# edge.net
KiCad netlist of a schematic drawn in Altium Designer
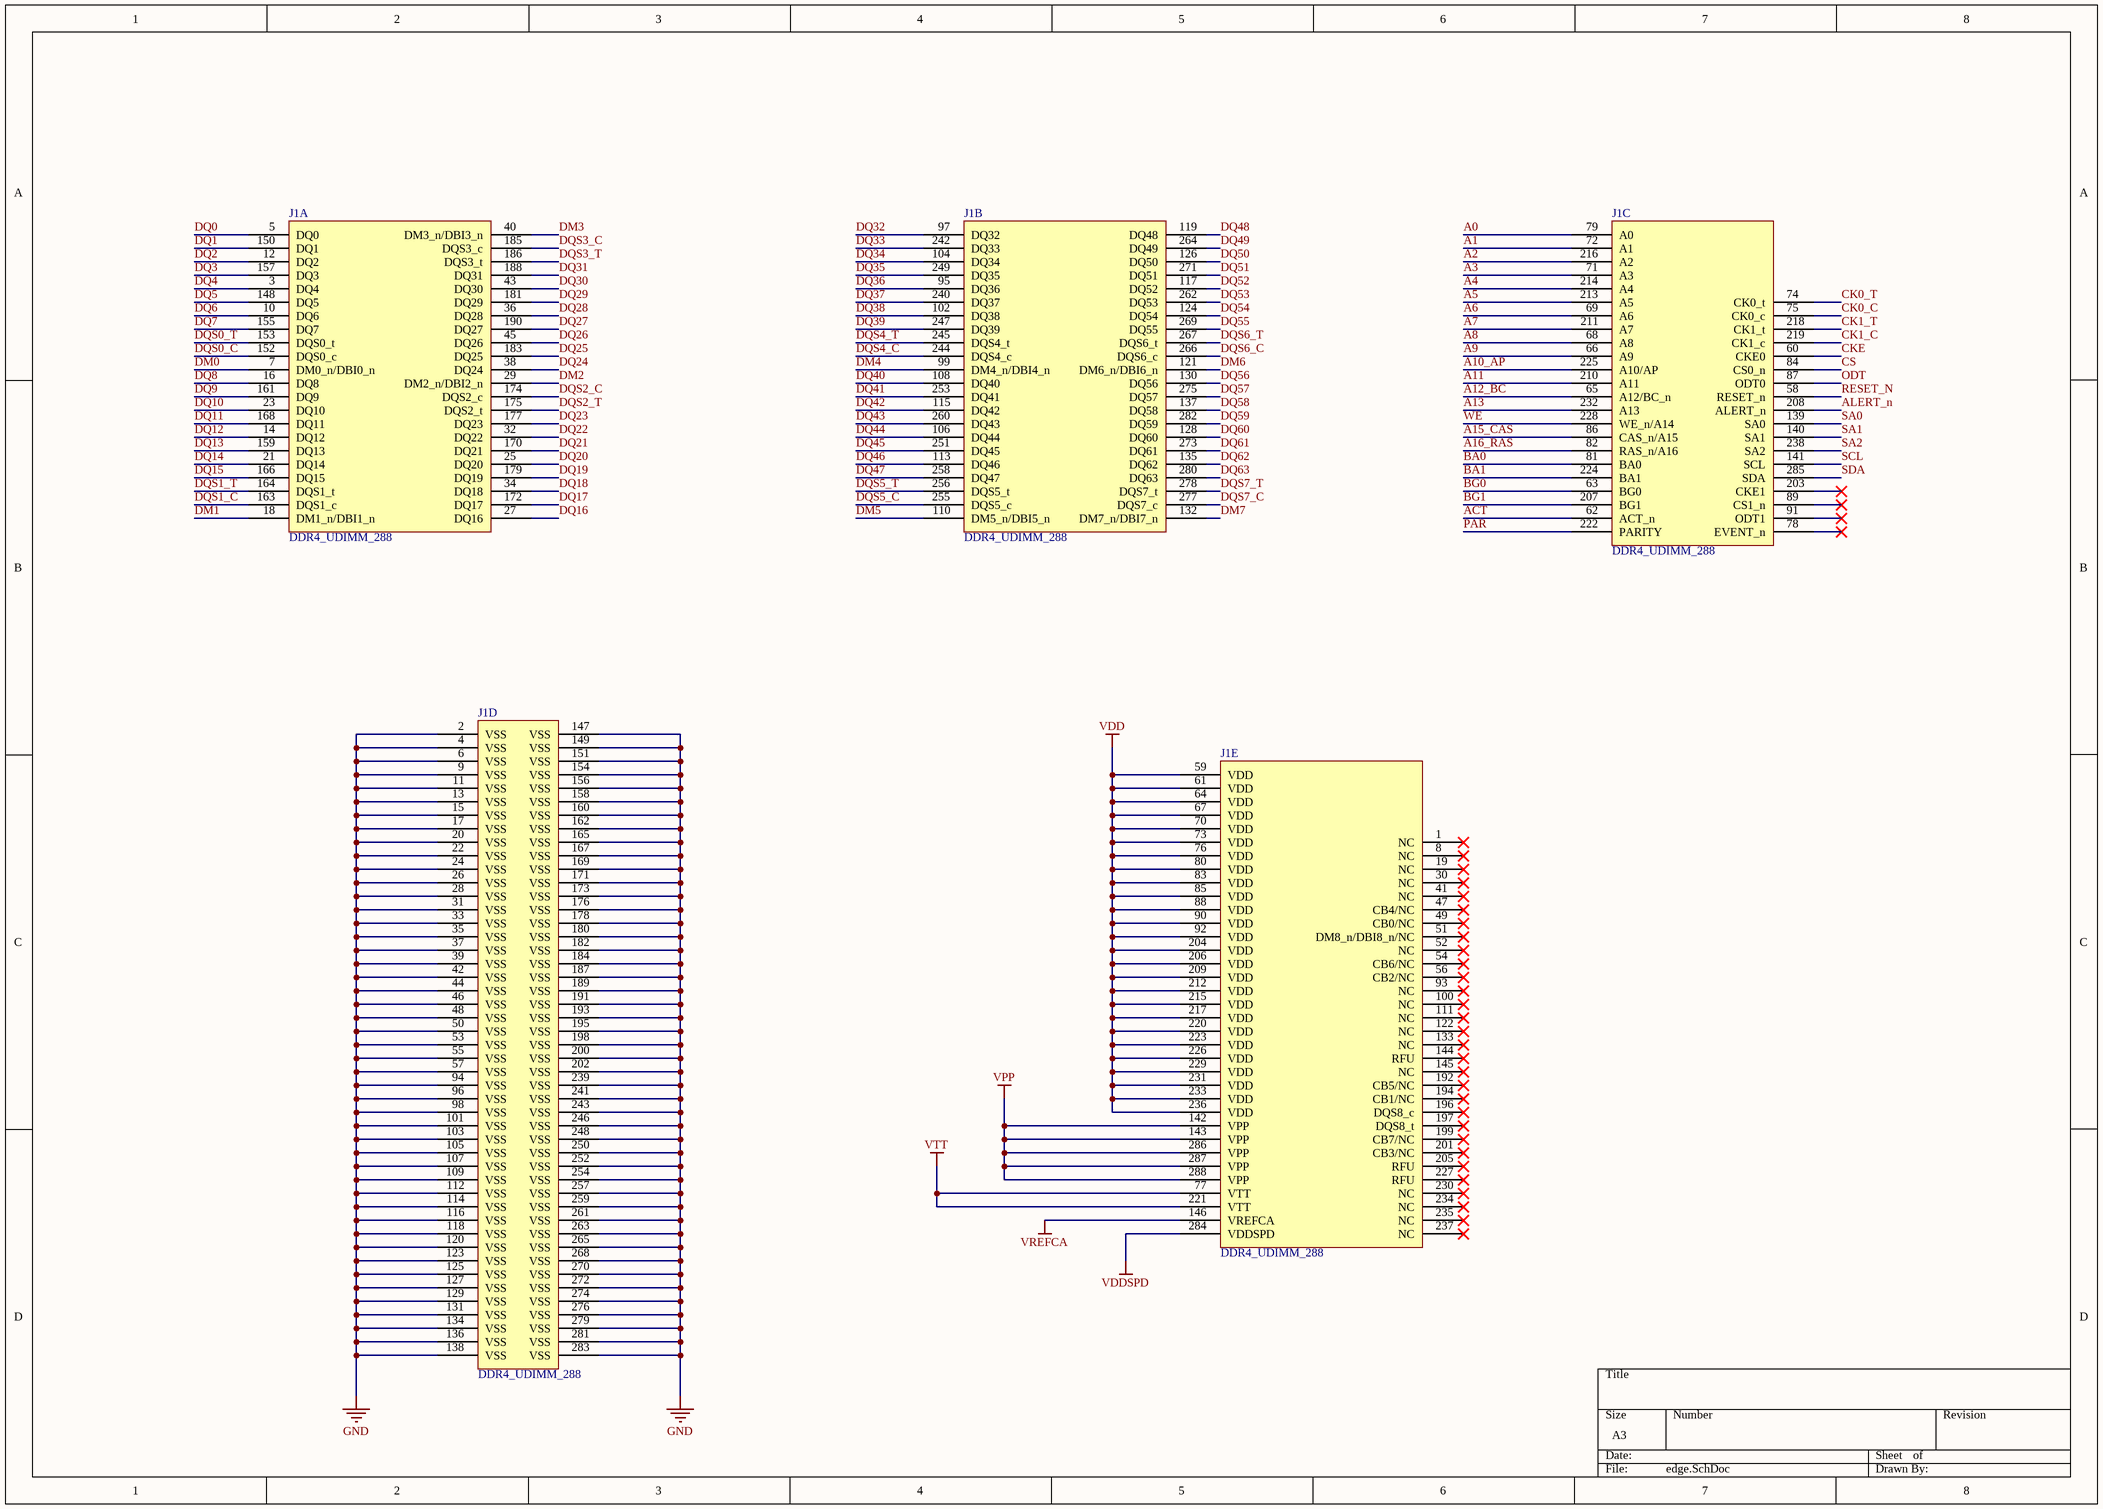
[diagram p0: edge.SchDoc]

(export (version "E")
  (design (tool "Eeschema 10.0.6"))
  (components
    (comp (ref "J1")
      (value "DDR4_UDIMM_288")
      (footprint "DDR4_UDIMM_288_MO309")
      (description "DDR4 288-pin UDIMM edge fingers, 0.85 mm pitch (JEDEC MO-309)")
      (libsource (lib "DDR4_UDIMM") (part "Component_1"))
    )
  )
  (nets
    (net (code "1") (name "/A0") (class "Default")
      (node (ref "J1") (pin "79") (pinfunction "A0_79") (pintype "passive"))
    )
    (net (code "2") (name "/A1") (class "Default")
      (node (ref "J1") (pin "72") (pinfunction "A1_72") (pintype "passive"))
    )
    (net (code "3") (name "/A2") (class "Default")
      (node (ref "J1") (pin "216") (pinfunction "A2_216") (pintype "passive"))
    )
    (net (code "4") (name "/A3") (class "Default")
      (node (ref "J1") (pin "71") (pinfunction "A3_71") (pintype "passive"))
    )
    (net (code "5") (name "/A4") (class "Default")
      (node (ref "J1") (pin "214") (pinfunction "A4_214") (pintype "passive"))
    )
    (net (code "6") (name "/A5") (class "Default")
      (node (ref "J1") (pin "213") (pinfunction "A5_213") (pintype "passive"))
    )
    (net (code "7") (name "/A6") (class "Default")
      (node (ref "J1") (pin "69") (pinfunction "A6_69") (pintype "passive"))
    )
    (net (code "8") (name "/A7") (class "Default")
      (node (ref "J1") (pin "211") (pinfunction "A7_211") (pintype "passive"))
    )
    (net (code "9") (name "/A8") (class "Default")
      (node (ref "J1") (pin "68") (pinfunction "A8_68") (pintype "passive"))
    )
    (net (code "10") (name "/A9") (class "Default")
      (node (ref "J1") (pin "66") (pinfunction "A9_66") (pintype "passive"))
    )
    (net (code "11") (name "/A10_AP") (class "Default")
      (node (ref "J1") (pin "225") (pinfunction "A10/AP_225") (pintype "passive"))
    )
    (net (code "12") (name "/A11") (class "Default")
      (node (ref "J1") (pin "210") (pinfunction "A11_210") (pintype "passive"))
    )
    (net (code "13") (name "/A12_BC") (class "Default")
      (node (ref "J1") (pin "65") (pinfunction "A12/BC_n_65") (pintype "passive"))
    )
    (net (code "14") (name "/A13") (class "Default")
      (node (ref "J1") (pin "232") (pinfunction "A13_232") (pintype "passive"))
    )
    (net (code "15") (name "/A15_CAS") (class "Default")
      (node (ref "J1") (pin "86") (pinfunction "CAS_n/A15_86") (pintype "passive"))
    )
    (net (code "16") (name "/A16_RAS") (class "Default")
      (node (ref "J1") (pin "82") (pinfunction "RAS_n/A16_82") (pintype "passive"))
    )
    (net (code "17") (name "/ACT") (class "Default")
      (node (ref "J1") (pin "62") (pinfunction "ACT_n_62") (pintype "passive"))
    )
    (net (code "18") (name "/ALERT_n") (class "Default")
      (node (ref "J1") (pin "208") (pinfunction "ALERT_n_208") (pintype "passive"))
    )
    (net (code "19") (name "/BA0") (class "Default")
      (node (ref "J1") (pin "81") (pinfunction "BA0_81") (pintype "passive"))
    )
    (net (code "20") (name "/BA1") (class "Default")
      (node (ref "J1") (pin "224") (pinfunction "BA1_224") (pintype "passive"))
    )
    (net (code "21") (name "/BG0") (class "Default")
      (node (ref "J1") (pin "63") (pinfunction "BG0_63") (pintype "passive"))
    )
    (net (code "22") (name "/BG1") (class "Default")
      (node (ref "J1") (pin "207") (pinfunction "BG1_207") (pintype "passive"))
    )
    (net (code "23") (name "/CK0_C") (class "Default")
      (node (ref "J1") (pin "75") (pinfunction "CK0_c_75") (pintype "passive"))
    )
    (net (code "24") (name "/CK0_T") (class "Default")
      (node (ref "J1") (pin "74") (pinfunction "CK0_t_74") (pintype "passive"))
    )
    (net (code "25") (name "/CK1_C") (class "Default")
      (node (ref "J1") (pin "219") (pinfunction "CK1_c_219") (pintype "passive"))
    )
    (net (code "26") (name "/CK1_T") (class "Default")
      (node (ref "J1") (pin "218") (pinfunction "CK1_t_218") (pintype "passive"))
    )
    (net (code "27") (name "/CKE") (class "Default")
      (node (ref "J1") (pin "60") (pinfunction "CKE0_60") (pintype "passive"))
    )
    (net (code "28") (name "/CS") (class "Default")
      (node (ref "J1") (pin "84") (pinfunction "CS0_n_84") (pintype "passive"))
    )
    (net (code "29") (name "/DM0") (class "Default")
      (node (ref "J1") (pin "7") (pinfunction "DM0_n/DBI0_n_7") (pintype "passive"))
    )
    (net (code "30") (name "/DM1") (class "Default")
      (node (ref "J1") (pin "18") (pinfunction "DM1_n/DBI1_n_18") (pintype "passive"))
    )
    (net (code "31") (name "/DM2") (class "Default")
      (node (ref "J1") (pin "29") (pinfunction "DM2_n/DBI2_n_29") (pintype "passive"))
    )
    (net (code "32") (name "/DM3") (class "Default")
      (node (ref "J1") (pin "40") (pinfunction "DM3_n/DBI3_n_40") (pintype "passive"))
    )
    (net (code "33") (name "/DM4") (class "Default")
      (node (ref "J1") (pin "99") (pinfunction "DM4_n/DBI4_n_99") (pintype "passive"))
    )
    (net (code "34") (name "/DM5") (class "Default")
      (node (ref "J1") (pin "110") (pinfunction "DM5_n/DBI5_n_110") (pintype "passive"))
    )
    (net (code "35") (name "/DM6") (class "Default")
      (node (ref "J1") (pin "121") (pinfunction "DM6_n/DBI6_n_121") (pintype "passive"))
    )
    (net (code "36") (name "/DM7") (class "Default")
      (node (ref "J1") (pin "132") (pinfunction "DM7_n/DBI7_n_132") (pintype "passive"))
    )
    (net (code "37") (name "/DQ0") (class "Default")
      (node (ref "J1") (pin "5") (pinfunction "DQ0_5") (pintype "passive"))
    )
    (net (code "38") (name "/DQ1") (class "Default")
      (node (ref "J1") (pin "150") (pinfunction "DQ1_150") (pintype "passive"))
    )
    (net (code "39") (name "/DQ2") (class "Default")
      (node (ref "J1") (pin "12") (pinfunction "DQ2_12") (pintype "passive"))
    )
    (net (code "40") (name "/DQ3") (class "Default")
      (node (ref "J1") (pin "157") (pinfunction "DQ3_157") (pintype "passive"))
    )
    (net (code "41") (name "/DQ4") (class "Default")
      (node (ref "J1") (pin "3") (pinfunction "DQ4_3") (pintype "passive"))
    )
    (net (code "42") (name "/DQ5") (class "Default")
      (node (ref "J1") (pin "148") (pinfunction "DQ5_148") (pintype "passive"))
    )
    (net (code "43") (name "/DQ6") (class "Default")
      (node (ref "J1") (pin "10") (pinfunction "DQ6_10") (pintype "passive"))
    )
    (net (code "44") (name "/DQ7") (class "Default")
      (node (ref "J1") (pin "155") (pinfunction "DQ7_155") (pintype "passive"))
    )
    (net (code "45") (name "/DQ8") (class "Default")
      (node (ref "J1") (pin "16") (pinfunction "DQ8_16") (pintype "passive"))
    )
    (net (code "46") (name "/DQ9") (class "Default")
      (node (ref "J1") (pin "161") (pinfunction "DQ9_161") (pintype "passive"))
    )
    (net (code "47") (name "/DQ10") (class "Default")
      (node (ref "J1") (pin "23") (pinfunction "DQ10_23") (pintype "passive"))
    )
    (net (code "48") (name "/DQ11") (class "Default")
      (node (ref "J1") (pin "168") (pinfunction "DQ11_168") (pintype "passive"))
    )
    (net (code "49") (name "/DQ12") (class "Default")
      (node (ref "J1") (pin "14") (pinfunction "DQ12_14") (pintype "passive"))
    )
    (net (code "50") (name "/DQ13") (class "Default")
      (node (ref "J1") (pin "159") (pinfunction "DQ13_159") (pintype "passive"))
    )
    (net (code "51") (name "/DQ14") (class "Default")
      (node (ref "J1") (pin "21") (pinfunction "DQ14_21") (pintype "passive"))
    )
    (net (code "52") (name "/DQ15") (class "Default")
      (node (ref "J1") (pin "166") (pinfunction "DQ15_166") (pintype "passive"))
    )
    (net (code "53") (name "/DQ16") (class "Default")
      (node (ref "J1") (pin "27") (pinfunction "DQ16_27") (pintype "passive"))
    )
    (net (code "54") (name "/DQ17") (class "Default")
      (node (ref "J1") (pin "172") (pinfunction "DQ17_172") (pintype "passive"))
    )
    (net (code "55") (name "/DQ18") (class "Default")
      (node (ref "J1") (pin "34") (pinfunction "DQ18_34") (pintype "passive"))
    )
    (net (code "56") (name "/DQ19") (class "Default")
      (node (ref "J1") (pin "179") (pinfunction "DQ19_179") (pintype "passive"))
    )
    (net (code "57") (name "/DQ20") (class "Default")
      (node (ref "J1") (pin "25") (pinfunction "DQ20_25") (pintype "passive"))
    )
    (net (code "58") (name "/DQ21") (class "Default")
      (node (ref "J1") (pin "170") (pinfunction "DQ21_170") (pintype "passive"))
    )
    (net (code "59") (name "/DQ22") (class "Default")
      (node (ref "J1") (pin "32") (pinfunction "DQ22_32") (pintype "passive"))
    )
    (net (code "60") (name "/DQ23") (class "Default")
      (node (ref "J1") (pin "177") (pinfunction "DQ23_177") (pintype "passive"))
    )
    (net (code "61") (name "/DQ24") (class "Default")
      (node (ref "J1") (pin "38") (pinfunction "DQ24_38") (pintype "passive"))
    )
    (net (code "62") (name "/DQ25") (class "Default")
      (node (ref "J1") (pin "183") (pinfunction "DQ25_183") (pintype "passive"))
    )
    (net (code "63") (name "/DQ26") (class "Default")
      (node (ref "J1") (pin "45") (pinfunction "DQ26_45") (pintype "passive"))
    )
    (net (code "64") (name "/DQ27") (class "Default")
      (node (ref "J1") (pin "190") (pinfunction "DQ27_190") (pintype "passive"))
    )
    (net (code "65") (name "/DQ28") (class "Default")
      (node (ref "J1") (pin "36") (pinfunction "DQ28_36") (pintype "passive"))
    )
    (net (code "66") (name "/DQ29") (class "Default")
      (node (ref "J1") (pin "181") (pinfunction "DQ29_181") (pintype "passive"))
    )
    (net (code "67") (name "/DQ30") (class "Default")
      (node (ref "J1") (pin "43") (pinfunction "DQ30_43") (pintype "passive"))
    )
    (net (code "68") (name "/DQ31") (class "Default")
      (node (ref "J1") (pin "188") (pinfunction "DQ31_188") (pintype "passive"))
    )
    (net (code "69") (name "/DQ32") (class "Default")
      (node (ref "J1") (pin "97") (pinfunction "DQ32_97") (pintype "passive"))
    )
    (net (code "70") (name "/DQ33") (class "Default")
      (node (ref "J1") (pin "242") (pinfunction "DQ33_242") (pintype "passive"))
    )
    (net (code "71") (name "/DQ34") (class "Default")
      (node (ref "J1") (pin "104") (pinfunction "DQ34_104") (pintype "passive"))
    )
    (net (code "72") (name "/DQ35") (class "Default")
      (node (ref "J1") (pin "249") (pinfunction "DQ35_249") (pintype "passive"))
    )
    (net (code "73") (name "/DQ36") (class "Default")
      (node (ref "J1") (pin "95") (pinfunction "DQ36_95") (pintype "passive"))
    )
    (net (code "74") (name "/DQ37") (class "Default")
      (node (ref "J1") (pin "240") (pinfunction "DQ37_240") (pintype "passive"))
    )
    (net (code "75") (name "/DQ38") (class "Default")
      (node (ref "J1") (pin "102") (pinfunction "DQ38_102") (pintype "passive"))
    )
    (net (code "76") (name "/DQ39") (class "Default")
      (node (ref "J1") (pin "247") (pinfunction "DQ39_247") (pintype "passive"))
    )
    (net (code "77") (name "/DQ40") (class "Default")
      (node (ref "J1") (pin "108") (pinfunction "DQ40_108") (pintype "passive"))
    )
    (net (code "78") (name "/DQ41") (class "Default")
      (node (ref "J1") (pin "253") (pinfunction "DQ41_253") (pintype "passive"))
    )
    (net (code "79") (name "/DQ42") (class "Default")
      (node (ref "J1") (pin "115") (pinfunction "DQ42_115") (pintype "passive"))
    )
    (net (code "80") (name "/DQ43") (class "Default")
      (node (ref "J1") (pin "260") (pinfunction "DQ43_260") (pintype "passive"))
    )
    (net (code "81") (name "/DQ44") (class "Default")
      (node (ref "J1") (pin "106") (pinfunction "DQ44_106") (pintype "passive"))
    )
    (net (code "82") (name "/DQ45") (class "Default")
      (node (ref "J1") (pin "251") (pinfunction "DQ45_251") (pintype "passive"))
    )
    (net (code "83") (name "/DQ46") (class "Default")
      (node (ref "J1") (pin "113") (pinfunction "DQ46_113") (pintype "passive"))
    )
    (net (code "84") (name "/DQ47") (class "Default")
      (node (ref "J1") (pin "258") (pinfunction "DQ47_258") (pintype "passive"))
    )
    (net (code "85") (name "/DQ48") (class "Default")
      (node (ref "J1") (pin "119") (pinfunction "DQ48_119") (pintype "passive"))
    )
    (net (code "86") (name "/DQ49") (class "Default")
      (node (ref "J1") (pin "264") (pinfunction "DQ49_264") (pintype "passive"))
    )
    (net (code "87") (name "/DQ50") (class "Default")
      (node (ref "J1") (pin "126") (pinfunction "DQ50_126") (pintype "passive"))
    )
    (net (code "88") (name "/DQ51") (class "Default")
      (node (ref "J1") (pin "271") (pinfunction "DQ51_271") (pintype "passive"))
    )
    (net (code "89") (name "/DQ52") (class "Default")
      (node (ref "J1") (pin "117") (pinfunction "DQ52_117") (pintype "passive"))
    )
    (net (code "90") (name "/DQ53") (class "Default")
      (node (ref "J1") (pin "262") (pinfunction "DQ53_262") (pintype "passive"))
    )
    (net (code "91") (name "/DQ54") (class "Default")
      (node (ref "J1") (pin "124") (pinfunction "DQ54_124") (pintype "passive"))
    )
    (net (code "92") (name "/DQ55") (class "Default")
      (node (ref "J1") (pin "269") (pinfunction "DQ55_269") (pintype "passive"))
    )
    (net (code "93") (name "/DQ56") (class "Default")
      (node (ref "J1") (pin "130") (pinfunction "DQ56_130") (pintype "passive"))
    )
    (net (code "94") (name "/DQ57") (class "Default")
      (node (ref "J1") (pin "275") (pinfunction "DQ57_275") (pintype "passive"))
    )
    (net (code "95") (name "/DQ58") (class "Default")
      (node (ref "J1") (pin "137") (pinfunction "DQ58_137") (pintype "passive"))
    )
    (net (code "96") (name "/DQ59") (class "Default")
      (node (ref "J1") (pin "282") (pinfunction "DQ59_282") (pintype "passive"))
    )
    (net (code "97") (name "/DQ60") (class "Default")
      (node (ref "J1") (pin "128") (pinfunction "DQ60_128") (pintype "passive"))
    )
    (net (code "98") (name "/DQ61") (class "Default")
      (node (ref "J1") (pin "273") (pinfunction "DQ61_273") (pintype "passive"))
    )
    (net (code "99") (name "/DQ62") (class "Default")
      (node (ref "J1") (pin "135") (pinfunction "DQ62_135") (pintype "passive"))
    )
    (net (code "100") (name "/DQ63") (class "Default")
      (node (ref "J1") (pin "280") (pinfunction "DQ63_280") (pintype "passive"))
    )
    (net (code "101") (name "/DQS0_C") (class "Default")
      (node (ref "J1") (pin "152") (pinfunction "DQS0_c_152") (pintype "passive"))
    )
    (net (code "102") (name "/DQS0_T") (class "Default")
      (node (ref "J1") (pin "153") (pinfunction "DQS0_t_153") (pintype "passive"))
    )
    (net (code "103") (name "/DQS1_C") (class "Default")
      (node (ref "J1") (pin "163") (pinfunction "DQS1_c_163") (pintype "passive"))
    )
    (net (code "104") (name "/DQS1_T") (class "Default")
      (node (ref "J1") (pin "164") (pinfunction "DQS1_t_164") (pintype "passive"))
    )
    (net (code "105") (name "/DQS2_C") (class "Default")
      (node (ref "J1") (pin "174") (pinfunction "DQS2_c_174") (pintype "passive"))
    )
    (net (code "106") (name "/DQS2_T") (class "Default")
      (node (ref "J1") (pin "175") (pinfunction "DQS2_t_175") (pintype "passive"))
    )
    (net (code "107") (name "/DQS3_C") (class "Default")
      (node (ref "J1") (pin "185") (pinfunction "DQS3_c_185") (pintype "passive"))
    )
    (net (code "108") (name "/DQS3_T") (class "Default")
      (node (ref "J1") (pin "186") (pinfunction "DQS3_t_186") (pintype "passive"))
    )
    (net (code "109") (name "/DQS4_C") (class "Default")
      (node (ref "J1") (pin "244") (pinfunction "DQS4_c_244") (pintype "passive"))
    )
    (net (code "110") (name "/DQS4_T") (class "Default")
      (node (ref "J1") (pin "245") (pinfunction "DQS4_t_245") (pintype "passive"))
    )
    (net (code "111") (name "/DQS5_C") (class "Default")
      (node (ref "J1") (pin "255") (pinfunction "DQS5_c_255") (pintype "passive"))
    )
    (net (code "112") (name "/DQS5_T") (class "Default")
      (node (ref "J1") (pin "256") (pinfunction "DQS5_t_256") (pintype "passive"))
    )
    (net (code "113") (name "/DQS6_C") (class "Default")
      (node (ref "J1") (pin "266") (pinfunction "DQS6_c_266") (pintype "passive"))
    )
    (net (code "114") (name "/DQS6_T") (class "Default")
      (node (ref "J1") (pin "267") (pinfunction "DQS6_t_267") (pintype "passive"))
    )
    (net (code "115") (name "/DQS7_C") (class "Default")
      (node (ref "J1") (pin "277") (pinfunction "DQS7_c_277") (pintype "passive"))
    )
    (net (code "116") (name "/DQS7_T") (class "Default")
      (node (ref "J1") (pin "278") (pinfunction "DQS7_t_278") (pintype "passive"))
    )
    (net (code "117") (name "/ODT") (class "Default")
      (node (ref "J1") (pin "87") (pinfunction "ODT0_87") (pintype "passive"))
    )
    (net (code "118") (name "/PAR") (class "Default")
      (node (ref "J1") (pin "222") (pinfunction "PARITY_222") (pintype "passive"))
    )
    (net (code "119") (name "/RESET_N") (class "Default")
      (node (ref "J1") (pin "58") (pinfunction "RESET_n_58") (pintype "passive"))
    )
    (net (code "120") (name "/SA0") (class "Default")
      (node (ref "J1") (pin "139") (pinfunction "SA0_139") (pintype "passive"))
    )
    (net (code "121") (name "/SA1") (class "Default")
      (node (ref "J1") (pin "140") (pinfunction "SA1_140") (pintype "passive"))
    )
    (net (code "122") (name "/SA2") (class "Default")
      (node (ref "J1") (pin "238") (pinfunction "SA2_238") (pintype "passive"))
    )
    (net (code "123") (name "/SCL") (class "Default")
      (node (ref "J1") (pin "141") (pinfunction "SCL_141") (pintype "passive"))
    )
    (net (code "124") (name "/SDA") (class "Default")
      (node (ref "J1") (pin "285") (pinfunction "SDA_285") (pintype "passive"))
    )
    (net (code "125") (name "/WE") (class "Default")
      (node (ref "J1") (pin "228") (pinfunction "WE_n/A14_228") (pintype "passive"))
    )
    (net (code "126") (name "GND") (class "Default")
      (node (ref "J1") (pin "101") (pinfunction "VSS_101") (pintype "passive"))
      (node (ref "J1") (pin "103") (pinfunction "VSS_103") (pintype "passive"))
      (node (ref "J1") (pin "105") (pinfunction "VSS_105") (pintype "passive"))
      (node (ref "J1") (pin "107") (pinfunction "VSS_107") (pintype "passive"))
      (node (ref "J1") (pin "109") (pinfunction "VSS_109") (pintype "passive"))
      (node (ref "J1") (pin "11") (pinfunction "VSS_11") (pintype "passive"))
      (node (ref "J1") (pin "112") (pinfunction "VSS_112") (pintype "passive"))
      (node (ref "J1") (pin "114") (pinfunction "VSS_114") (pintype "passive"))
      (node (ref "J1") (pin "116") (pinfunction "VSS_116") (pintype "passive"))
      (node (ref "J1") (pin "118") (pinfunction "VSS_118") (pintype "passive"))
      (node (ref "J1") (pin "120") (pinfunction "VSS_120") (pintype "passive"))
      (node (ref "J1") (pin "123") (pinfunction "VSS_123") (pintype "passive"))
      (node (ref "J1") (pin "125") (pinfunction "VSS_125") (pintype "passive"))
      (node (ref "J1") (pin "127") (pinfunction "VSS_127") (pintype "passive"))
      (node (ref "J1") (pin "129") (pinfunction "VSS_129") (pintype "passive"))
      (node (ref "J1") (pin "13") (pinfunction "VSS_13") (pintype "passive"))
      (node (ref "J1") (pin "131") (pinfunction "VSS_131") (pintype "passive"))
      (node (ref "J1") (pin "134") (pinfunction "VSS_134") (pintype "passive"))
      (node (ref "J1") (pin "136") (pinfunction "VSS_136") (pintype "passive"))
      (node (ref "J1") (pin "138") (pinfunction "VSS_138") (pintype "passive"))
      (node (ref "J1") (pin "147") (pinfunction "VSS_147") (pintype "passive"))
      (node (ref "J1") (pin "149") (pinfunction "VSS_149") (pintype "passive"))
      (node (ref "J1") (pin "15") (pinfunction "VSS_15") (pintype "passive"))
      (node (ref "J1") (pin "151") (pinfunction "VSS_151") (pintype "passive"))
      (node (ref "J1") (pin "154") (pinfunction "VSS_154") (pintype "passive"))
      (node (ref "J1") (pin "156") (pinfunction "VSS_156") (pintype "passive"))
      (node (ref "J1") (pin "158") (pinfunction "VSS_158") (pintype "passive"))
      (node (ref "J1") (pin "160") (pinfunction "VSS_160") (pintype "passive"))
      (node (ref "J1") (pin "162") (pinfunction "VSS_162") (pintype "passive"))
      (node (ref "J1") (pin "165") (pinfunction "VSS_165") (pintype "passive"))
      (node (ref "J1") (pin "167") (pinfunction "VSS_167") (pintype "passive"))
      (node (ref "J1") (pin "169") (pinfunction "VSS_169") (pintype "passive"))
      (node (ref "J1") (pin "17") (pinfunction "VSS_17") (pintype "passive"))
      (node (ref "J1") (pin "171") (pinfunction "VSS_171") (pintype "passive"))
      (node (ref "J1") (pin "173") (pinfunction "VSS_173") (pintype "passive"))
      (node (ref "J1") (pin "176") (pinfunction "VSS_176") (pintype "passive"))
      (node (ref "J1") (pin "178") (pinfunction "VSS_178") (pintype "passive"))
      (node (ref "J1") (pin "180") (pinfunction "VSS_180") (pintype "passive"))
      (node (ref "J1") (pin "182") (pinfunction "VSS_182") (pintype "passive"))
      (node (ref "J1") (pin "184") (pinfunction "VSS_184") (pintype "passive"))
      (node (ref "J1") (pin "187") (pinfunction "VSS_187") (pintype "passive"))
      (node (ref "J1") (pin "189") (pinfunction "VSS_189") (pintype "passive"))
      (node (ref "J1") (pin "191") (pinfunction "VSS_191") (pintype "passive"))
      (node (ref "J1") (pin "193") (pinfunction "VSS_193") (pintype "passive"))
      (node (ref "J1") (pin "195") (pinfunction "VSS_195") (pintype "passive"))
      (node (ref "J1") (pin "198") (pinfunction "VSS_198") (pintype "passive"))
      (node (ref "J1") (pin "2") (pinfunction "VSS_2") (pintype "passive"))
      (node (ref "J1") (pin "20") (pinfunction "VSS_20") (pintype "passive"))
      (node (ref "J1") (pin "200") (pinfunction "VSS_200") (pintype "passive"))
      (node (ref "J1") (pin "202") (pinfunction "VSS_202") (pintype "passive"))
      (node (ref "J1") (pin "22") (pinfunction "VSS_22") (pintype "passive"))
      (node (ref "J1") (pin "239") (pinfunction "VSS_239") (pintype "passive"))
      (node (ref "J1") (pin "24") (pinfunction "VSS_24") (pintype "passive"))
      (node (ref "J1") (pin "241") (pinfunction "VSS_241") (pintype "passive"))
      (node (ref "J1") (pin "243") (pinfunction "VSS_243") (pintype "passive"))
      (node (ref "J1") (pin "246") (pinfunction "VSS_246") (pintype "passive"))
      (node (ref "J1") (pin "248") (pinfunction "VSS_248") (pintype "passive"))
      (node (ref "J1") (pin "250") (pinfunction "VSS_250") (pintype "passive"))
      (node (ref "J1") (pin "252") (pinfunction "VSS_252") (pintype "passive"))
      (node (ref "J1") (pin "254") (pinfunction "VSS_254") (pintype "passive"))
      (node (ref "J1") (pin "257") (pinfunction "VSS_257") (pintype "passive"))
      (node (ref "J1") (pin "259") (pinfunction "VSS_259") (pintype "passive"))
      (node (ref "J1") (pin "26") (pinfunction "VSS_26") (pintype "passive"))
      (node (ref "J1") (pin "261") (pinfunction "VSS_261") (pintype "passive"))
      (node (ref "J1") (pin "263") (pinfunction "VSS_263") (pintype "passive"))
      (node (ref "J1") (pin "265") (pinfunction "VSS_265") (pintype "passive"))
      (node (ref "J1") (pin "268") (pinfunction "VSS_268") (pintype "passive"))
      (node (ref "J1") (pin "270") (pinfunction "VSS_270") (pintype "passive"))
      (node (ref "J1") (pin "272") (pinfunction "VSS_272") (pintype "passive"))
      (node (ref "J1") (pin "274") (pinfunction "VSS_274") (pintype "passive"))
      (node (ref "J1") (pin "276") (pinfunction "VSS_276") (pintype "passive"))
      (node (ref "J1") (pin "279") (pinfunction "VSS_279") (pintype "passive"))
      (node (ref "J1") (pin "28") (pinfunction "VSS_28") (pintype "passive"))
      (node (ref "J1") (pin "281") (pinfunction "VSS_281") (pintype "passive"))
      (node (ref "J1") (pin "283") (pinfunction "VSS_283") (pintype "passive"))
      (node (ref "J1") (pin "31") (pinfunction "VSS_31") (pintype "passive"))
      (node (ref "J1") (pin "33") (pinfunction "VSS_33") (pintype "passive"))
      (node (ref "J1") (pin "35") (pinfunction "VSS_35") (pintype "passive"))
      (node (ref "J1") (pin "37") (pinfunction "VSS_37") (pintype "passive"))
      (node (ref "J1") (pin "39") (pinfunction "VSS_39") (pintype "passive"))
      (node (ref "J1") (pin "4") (pinfunction "VSS_4") (pintype "passive"))
      (node (ref "J1") (pin "42") (pinfunction "VSS_42") (pintype "passive"))
      (node (ref "J1") (pin "44") (pinfunction "VSS_44") (pintype "passive"))
      (node (ref "J1") (pin "46") (pinfunction "VSS_46") (pintype "passive"))
      (node (ref "J1") (pin "48") (pinfunction "VSS_48") (pintype "passive"))
      (node (ref "J1") (pin "50") (pinfunction "VSS_50") (pintype "passive"))
      (node (ref "J1") (pin "53") (pinfunction "VSS_53") (pintype "passive"))
      (node (ref "J1") (pin "55") (pinfunction "VSS_55") (pintype "passive"))
      (node (ref "J1") (pin "57") (pinfunction "VSS_57") (pintype "passive"))
      (node (ref "J1") (pin "6") (pinfunction "VSS_6") (pintype "passive"))
      (node (ref "J1") (pin "9") (pinfunction "VSS_9") (pintype "passive"))
      (node (ref "J1") (pin "94") (pinfunction "VSS_94") (pintype "passive"))
      (node (ref "J1") (pin "96") (pinfunction "VSS_96") (pintype "passive"))
      (node (ref "J1") (pin "98") (pinfunction "VSS_98") (pintype "passive"))
    )
    (net (code "127") (name "VDD") (class "Default")
      (node (ref "J1") (pin "204") (pinfunction "VDD_204") (pintype "passive"))
      (node (ref "J1") (pin "206") (pinfunction "VDD_206") (pintype "passive"))
      (node (ref "J1") (pin "209") (pinfunction "VDD_209") (pintype "passive"))
      (node (ref "J1") (pin "212") (pinfunction "VDD_212") (pintype "passive"))
      (node (ref "J1") (pin "215") (pinfunction "VDD_215") (pintype "passive"))
      (node (ref "J1") (pin "217") (pinfunction "VDD_217") (pintype "passive"))
      (node (ref "J1") (pin "220") (pinfunction "VDD_220") (pintype "passive"))
      (node (ref "J1") (pin "223") (pinfunction "VDD_223") (pintype "passive"))
      (node (ref "J1") (pin "226") (pinfunction "VDD_226") (pintype "passive"))
      (node (ref "J1") (pin "229") (pinfunction "VDD_229") (pintype "passive"))
      (node (ref "J1") (pin "231") (pinfunction "VDD_231") (pintype "passive"))
      (node (ref "J1") (pin "233") (pinfunction "VDD_233") (pintype "passive"))
      (node (ref "J1") (pin "236") (pinfunction "VDD_236") (pintype "passive"))
      (node (ref "J1") (pin "59") (pinfunction "VDD_59") (pintype "passive"))
      (node (ref "J1") (pin "61") (pinfunction "VDD_61") (pintype "passive"))
      (node (ref "J1") (pin "64") (pinfunction "VDD_64") (pintype "passive"))
      (node (ref "J1") (pin "67") (pinfunction "VDD_67") (pintype "passive"))
      (node (ref "J1") (pin "70") (pinfunction "VDD_70") (pintype "passive"))
      (node (ref "J1") (pin "73") (pinfunction "VDD_73") (pintype "passive"))
      (node (ref "J1") (pin "76") (pinfunction "VDD_76") (pintype "passive"))
      (node (ref "J1") (pin "80") (pinfunction "VDD_80") (pintype "passive"))
      (node (ref "J1") (pin "83") (pinfunction "VDD_83") (pintype "passive"))
      (node (ref "J1") (pin "85") (pinfunction "VDD_85") (pintype "passive"))
      (node (ref "J1") (pin "88") (pinfunction "VDD_88") (pintype "passive"))
      (node (ref "J1") (pin "90") (pinfunction "VDD_90") (pintype "passive"))
      (node (ref "J1") (pin "92") (pinfunction "VDD_92") (pintype "passive"))
    )
    (net (code "128") (name "VDDSPD") (class "Default")
      (node (ref "J1") (pin "284") (pinfunction "VDDSPD_284") (pintype "passive"))
    )
    (net (code "129") (name "VPP") (class "Default")
      (node (ref "J1") (pin "142") (pinfunction "VPP_142") (pintype "passive"))
      (node (ref "J1") (pin "143") (pinfunction "VPP_143") (pintype "passive"))
      (node (ref "J1") (pin "286") (pinfunction "VPP_286") (pintype "passive"))
      (node (ref "J1") (pin "287") (pinfunction "VPP_287") (pintype "passive"))
      (node (ref "J1") (pin "288") (pinfunction "VPP_288") (pintype "passive"))
    )
    (net (code "130") (name "VREFCA") (class "Default")
      (node (ref "J1") (pin "146") (pinfunction "VREFCA_146") (pintype "passive"))
    )
    (net (code "131") (name "VTT") (class "Default")
      (node (ref "J1") (pin "221") (pinfunction "VTT_221") (pintype "passive"))
      (node (ref "J1") (pin "77") (pinfunction "VTT_77") (pintype "passive"))
    )
    (net (code "132") (name "unconnected-(J1C-CKE1-Pad203)") (class "Default")
      (node (ref "J1") (pin "203") (pinfunction "CKE1_203") (pintype "passive+no_connect"))
    )
    (net (code "133") (name "unconnected-(J1C-CS1_n-Pad89)") (class "Default")
      (node (ref "J1") (pin "89") (pinfunction "CS1_n_89") (pintype "passive+no_connect"))
    )
    (net (code "134") (name "unconnected-(J1C-EVENT_n-Pad78)") (class "Default")
      (node (ref "J1") (pin "78") (pinfunction "EVENT_n_78") (pintype "passive+no_connect"))
    )
    (net (code "135") (name "unconnected-(J1C-ODT1-Pad91)") (class "Default")
      (node (ref "J1") (pin "91") (pinfunction "ODT1_91") (pintype "passive+no_connect"))
    )
    (net (code "136") (name "unconnected-(J1E-CB0{slash}NC-Pad49)") (class "Default")
      (node (ref "J1") (pin "49") (pinfunction "CB0/NC_49") (pintype "passive+no_connect"))
    )
    (net (code "137") (name "unconnected-(J1E-CB1{slash}NC-Pad194)") (class "Default")
      (node (ref "J1") (pin "194") (pinfunction "CB1/NC_194") (pintype "passive+no_connect"))
    )
    (net (code "138") (name "unconnected-(J1E-CB2{slash}NC-Pad56)") (class "Default")
      (node (ref "J1") (pin "56") (pinfunction "CB2/NC_56") (pintype "passive+no_connect"))
    )
    (net (code "139") (name "unconnected-(J1E-CB3{slash}NC-Pad201)") (class "Default")
      (node (ref "J1") (pin "201") (pinfunction "CB3/NC_201") (pintype "passive+no_connect"))
    )
    (net (code "140") (name "unconnected-(J1E-CB4{slash}NC-Pad47)") (class "Default")
      (node (ref "J1") (pin "47") (pinfunction "CB4/NC_47") (pintype "passive+no_connect"))
    )
    (net (code "141") (name "unconnected-(J1E-CB5{slash}NC-Pad192)") (class "Default")
      (node (ref "J1") (pin "192") (pinfunction "CB5/NC_192") (pintype "passive+no_connect"))
    )
    (net (code "142") (name "unconnected-(J1E-CB6{slash}NC-Pad54)") (class "Default")
      (node (ref "J1") (pin "54") (pinfunction "CB6/NC_54") (pintype "passive+no_connect"))
    )
    (net (code "143") (name "unconnected-(J1E-CB7{slash}NC-Pad199)") (class "Default")
      (node (ref "J1") (pin "199") (pinfunction "CB7/NC_199") (pintype "passive+no_connect"))
    )
    (net (code "144") (name "unconnected-(J1E-DM8_n{slash}DBI8_n{slash}NC-Pad51)") (class "Default")
      (node (ref "J1") (pin "51") (pinfunction "DM8_n/DBI8_n/NC_51") (pintype "passive+no_connect"))
    )
    (net (code "145") (name "unconnected-(J1E-DQS8_c-Pad196)") (class "Default")
      (node (ref "J1") (pin "196") (pinfunction "DQS8_c_196") (pintype "passive+no_connect"))
    )
    (net (code "146") (name "unconnected-(J1E-DQS8_t-Pad197)") (class "Default")
      (node (ref "J1") (pin "197") (pinfunction "DQS8_t_197") (pintype "passive+no_connect"))
    )
    (net (code "147") (name "unconnected-(J1E-NC-Pad1)") (class "Default")
      (node (ref "J1") (pin "1") (pinfunction "NC_1") (pintype "passive+no_connect"))
    )
    (net (code "148") (name "unconnected-(J1E-NC-Pad8)") (class "Default")
      (node (ref "J1") (pin "8") (pinfunction "NC_8") (pintype "passive+no_connect"))
    )
    (net (code "149") (name "unconnected-(J1E-NC-Pad19)") (class "Default")
      (node (ref "J1") (pin "19") (pinfunction "NC_19") (pintype "passive+no_connect"))
    )
    (net (code "150") (name "unconnected-(J1E-NC-Pad30)") (class "Default")
      (node (ref "J1") (pin "30") (pinfunction "NC_30") (pintype "passive+no_connect"))
    )
    (net (code "151") (name "unconnected-(J1E-NC-Pad41)") (class "Default")
      (node (ref "J1") (pin "41") (pinfunction "NC_41") (pintype "passive+no_connect"))
    )
    (net (code "152") (name "unconnected-(J1E-NC-Pad52)") (class "Default")
      (node (ref "J1") (pin "52") (pinfunction "NC_52") (pintype "passive+no_connect"))
    )
    (net (code "153") (name "unconnected-(J1E-NC-Pad93)") (class "Default")
      (node (ref "J1") (pin "93") (pinfunction "NC_93") (pintype "passive+no_connect"))
    )
    (net (code "154") (name "unconnected-(J1E-NC-Pad100)") (class "Default")
      (node (ref "J1") (pin "100") (pinfunction "NC_100") (pintype "passive+no_connect"))
    )
    (net (code "155") (name "unconnected-(J1E-NC-Pad111)") (class "Default")
      (node (ref "J1") (pin "111") (pinfunction "NC_111") (pintype "passive+no_connect"))
    )
    (net (code "156") (name "unconnected-(J1E-NC-Pad122)") (class "Default")
      (node (ref "J1") (pin "122") (pinfunction "NC_122") (pintype "passive+no_connect"))
    )
    (net (code "157") (name "unconnected-(J1E-NC-Pad133)") (class "Default")
      (node (ref "J1") (pin "133") (pinfunction "NC_133") (pintype "passive+no_connect"))
    )
    (net (code "158") (name "unconnected-(J1E-NC-Pad145)") (class "Default")
      (node (ref "J1") (pin "145") (pinfunction "NC_145") (pintype "passive+no_connect"))
    )
    (net (code "159") (name "unconnected-(J1E-NC-Pad230)") (class "Default")
      (node (ref "J1") (pin "230") (pinfunction "NC_230") (pintype "passive+no_connect"))
    )
    (net (code "160") (name "unconnected-(J1E-NC-Pad234)") (class "Default")
      (node (ref "J1") (pin "234") (pinfunction "NC_234") (pintype "passive+no_connect"))
    )
    (net (code "161") (name "unconnected-(J1E-NC-Pad235)") (class "Default")
      (node (ref "J1") (pin "235") (pinfunction "NC_235") (pintype "passive+no_connect"))
    )
    (net (code "162") (name "unconnected-(J1E-NC-Pad237)") (class "Default")
      (node (ref "J1") (pin "237") (pinfunction "NC_237") (pintype "passive+no_connect"))
    )
    (net (code "163") (name "unconnected-(J1E-RFU-Pad144)") (class "Default")
      (node (ref "J1") (pin "144") (pinfunction "RFU_144") (pintype "passive+no_connect"))
    )
    (net (code "164") (name "unconnected-(J1E-RFU-Pad205)") (class "Default")
      (node (ref "J1") (pin "205") (pinfunction "RFU_205") (pintype "passive+no_connect"))
    )
    (net (code "165") (name "unconnected-(J1E-RFU-Pad227)") (class "Default")
      (node (ref "J1") (pin "227") (pinfunction "RFU_227") (pintype "passive+no_connect"))
    )
  )
)
